# relays0.net
KiCad netlist of a schematic drawn in Altium Designer
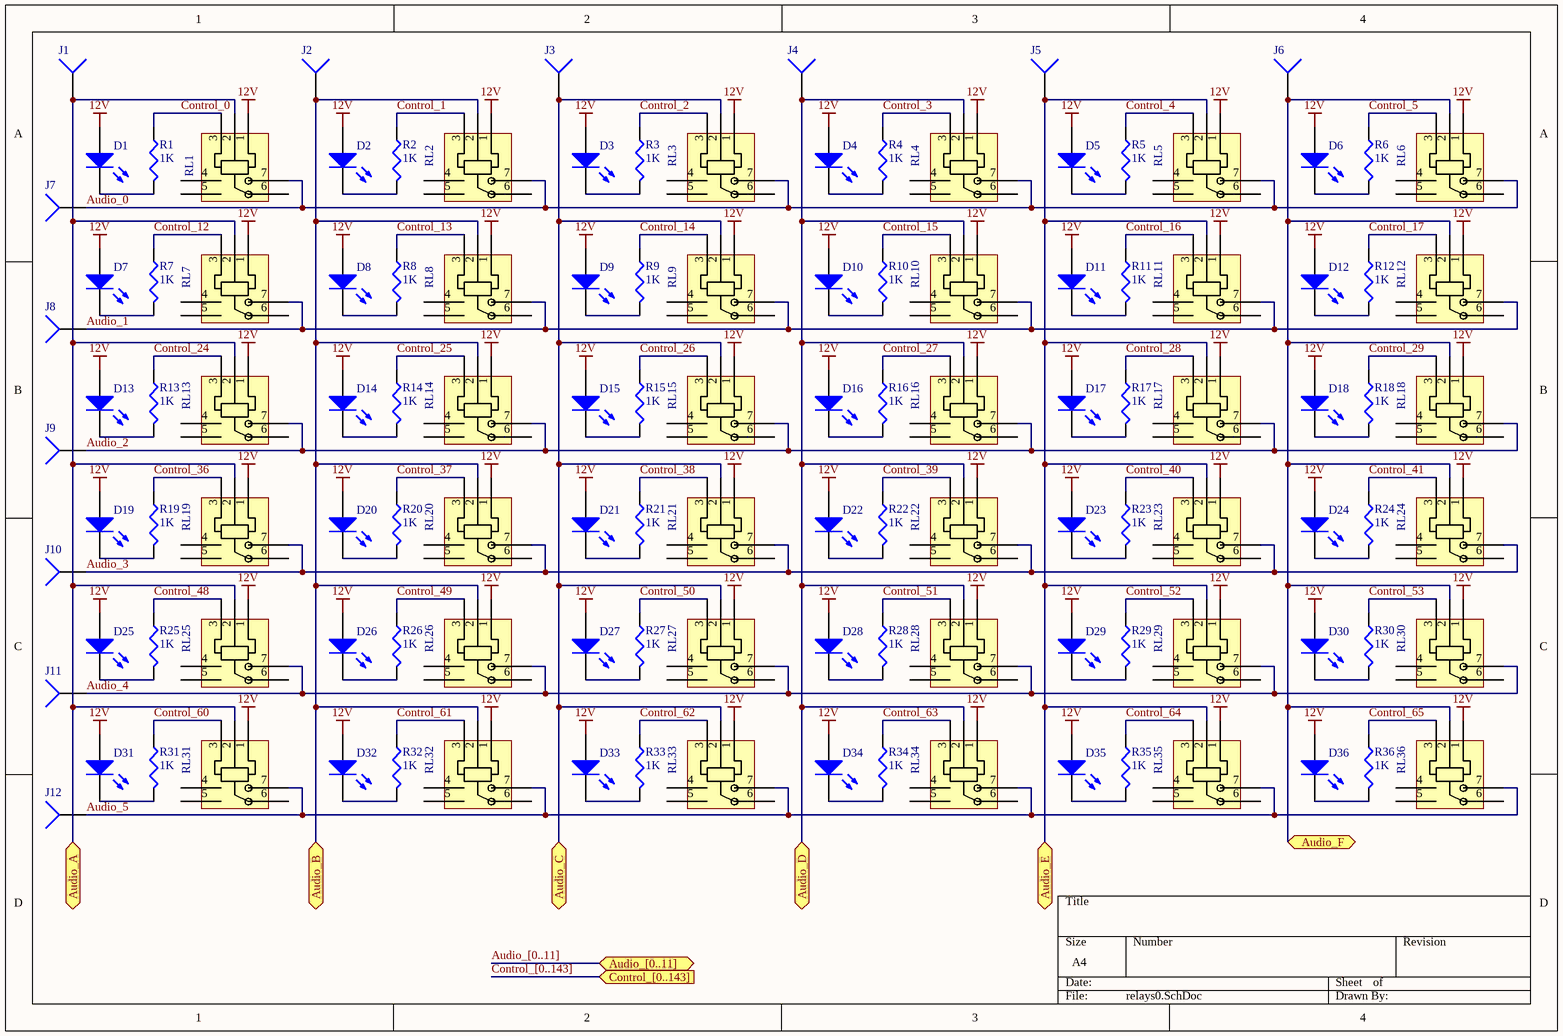
[diagram p0: relays0.SchDoc]

(export (version "E")
  (design (tool "Eeschema 10.0.6"))
  (components
    (comp (ref "D1")
      (value "LED0")
      (footprint "LED_round_5mm")
      (description "Typical INFRARED GaAs LED")
      (fields (field (name "PUBLISHER") "Altium Limited"))
      (libsource (lib "Miscellaneous Devices") (part "LED0"))
    )
    (comp (ref "D2")
      (value "LED0")
      (footprint "LED_round_5mm")
      (description "Typical INFRARED GaAs LED")
      (fields (field (name "PUBLISHER") "Altium Limited"))
      (libsource (lib "Miscellaneous Devices") (part "LED0"))
    )
    (comp (ref "D3")
      (value "LED0")
      (footprint "LED_round_5mm")
      (description "Typical INFRARED GaAs LED")
      (fields (field (name "PUBLISHER") "Altium Limited"))
      (libsource (lib "Miscellaneous Devices") (part "LED0"))
    )
    (comp (ref "D4")
      (value "LED0")
      (footprint "LED_round_5mm")
      (description "Typical INFRARED GaAs LED")
      (fields (field (name "PUBLISHER") "Altium Limited"))
      (libsource (lib "Miscellaneous Devices") (part "LED0"))
    )
    (comp (ref "D5")
      (value "LED0")
      (footprint "LED_round_5mm")
      (description "Typical INFRARED GaAs LED")
      (fields (field (name "PUBLISHER") "Altium Limited"))
      (libsource (lib "Miscellaneous Devices") (part "LED0"))
    )
    (comp (ref "D6")
      (value "LED0")
      (footprint "LED_round_5mm")
      (description "Typical INFRARED GaAs LED")
      (fields (field (name "PUBLISHER") "Altium Limited"))
      (libsource (lib "Miscellaneous Devices") (part "LED0"))
    )
    (comp (ref "D7")
      (value "LED0")
      (footprint "LED_round_5mm")
      (description "Typical INFRARED GaAs LED")
      (fields (field (name "PUBLISHER") "Altium Limited"))
      (libsource (lib "Miscellaneous Devices") (part "LED0"))
    )
    (comp (ref "D8")
      (value "LED0")
      (footprint "LED_round_5mm")
      (description "Typical INFRARED GaAs LED")
      (fields (field (name "PUBLISHER") "Altium Limited"))
      (libsource (lib "Miscellaneous Devices") (part "LED0"))
    )
    (comp (ref "D9")
      (value "LED0")
      (footprint "LED_round_5mm")
      (description "Typical INFRARED GaAs LED")
      (fields (field (name "PUBLISHER") "Altium Limited"))
      (libsource (lib "Miscellaneous Devices") (part "LED0"))
    )
    (comp (ref "D10")
      (value "LED0")
      (footprint "LED_round_5mm")
      (description "Typical INFRARED GaAs LED")
      (fields (field (name "PUBLISHER") "Altium Limited"))
      (libsource (lib "Miscellaneous Devices") (part "LED0"))
    )
    (comp (ref "D11")
      (value "LED0")
      (footprint "LED_round_5mm")
      (description "Typical INFRARED GaAs LED")
      (fields (field (name "PUBLISHER") "Altium Limited"))
      (libsource (lib "Miscellaneous Devices") (part "LED0"))
    )
    (comp (ref "D12")
      (value "LED0")
      (footprint "LED_round_5mm")
      (description "Typical INFRARED GaAs LED")
      (fields (field (name "PUBLISHER") "Altium Limited"))
      (libsource (lib "Miscellaneous Devices") (part "LED0"))
    )
    (comp (ref "D13")
      (value "LED0")
      (footprint "LED_round_5mm")
      (description "Typical INFRARED GaAs LED")
      (fields (field (name "PUBLISHER") "Altium Limited"))
      (libsource (lib "Miscellaneous Devices") (part "LED0"))
    )
    (comp (ref "D14")
      (value "LED0")
      (footprint "LED_round_5mm")
      (description "Typical INFRARED GaAs LED")
      (fields (field (name "PUBLISHER") "Altium Limited"))
      (libsource (lib "Miscellaneous Devices") (part "LED0"))
    )
    (comp (ref "D15")
      (value "LED0")
      (footprint "LED_round_5mm")
      (description "Typical INFRARED GaAs LED")
      (fields (field (name "PUBLISHER") "Altium Limited"))
      (libsource (lib "Miscellaneous Devices") (part "LED0"))
    )
    (comp (ref "D16")
      (value "LED0")
      (footprint "LED_round_5mm")
      (description "Typical INFRARED GaAs LED")
      (fields (field (name "PUBLISHER") "Altium Limited"))
      (libsource (lib "Miscellaneous Devices") (part "LED0"))
    )
    (comp (ref "D17")
      (value "LED0")
      (footprint "LED_round_5mm")
      (description "Typical INFRARED GaAs LED")
      (fields (field (name "PUBLISHER") "Altium Limited"))
      (libsource (lib "Miscellaneous Devices") (part "LED0"))
    )
    (comp (ref "D18")
      (value "LED0")
      (footprint "LED_round_5mm")
      (description "Typical INFRARED GaAs LED")
      (fields (field (name "PUBLISHER") "Altium Limited"))
      (libsource (lib "Miscellaneous Devices") (part "LED0"))
    )
    (comp (ref "D19")
      (value "LED0")
      (footprint "LED_round_5mm")
      (description "Typical INFRARED GaAs LED")
      (fields (field (name "PUBLISHER") "Altium Limited"))
      (libsource (lib "Miscellaneous Devices") (part "LED0"))
    )
    (comp (ref "D20")
      (value "LED0")
      (footprint "LED_round_5mm")
      (description "Typical INFRARED GaAs LED")
      (fields (field (name "PUBLISHER") "Altium Limited"))
      (libsource (lib "Miscellaneous Devices") (part "LED0"))
    )
    (comp (ref "D21")
      (value "LED0")
      (footprint "LED_round_5mm")
      (description "Typical INFRARED GaAs LED")
      (fields (field (name "PUBLISHER") "Altium Limited"))
      (libsource (lib "Miscellaneous Devices") (part "LED0"))
    )
    (comp (ref "D22")
      (value "LED0")
      (footprint "LED_round_5mm")
      (description "Typical INFRARED GaAs LED")
      (fields (field (name "PUBLISHER") "Altium Limited"))
      (libsource (lib "Miscellaneous Devices") (part "LED0"))
    )
    (comp (ref "D23")
      (value "LED0")
      (footprint "LED_round_5mm")
      (description "Typical INFRARED GaAs LED")
      (fields (field (name "PUBLISHER") "Altium Limited"))
      (libsource (lib "Miscellaneous Devices") (part "LED0"))
    )
    (comp (ref "D24")
      (value "LED0")
      (footprint "LED_round_5mm")
      (description "Typical INFRARED GaAs LED")
      (fields (field (name "PUBLISHER") "Altium Limited"))
      (libsource (lib "Miscellaneous Devices") (part "LED0"))
    )
    (comp (ref "D25")
      (value "LED0")
      (footprint "LED_round_5mm")
      (description "Typical INFRARED GaAs LED")
      (fields (field (name "PUBLISHER") "Altium Limited"))
      (libsource (lib "Miscellaneous Devices") (part "LED0"))
    )
    (comp (ref "D26")
      (value "LED0")
      (footprint "LED_round_5mm")
      (description "Typical INFRARED GaAs LED")
      (fields (field (name "PUBLISHER") "Altium Limited"))
      (libsource (lib "Miscellaneous Devices") (part "LED0"))
    )
    (comp (ref "D27")
      (value "LED0")
      (footprint "LED_round_5mm")
      (description "Typical INFRARED GaAs LED")
      (fields (field (name "PUBLISHER") "Altium Limited"))
      (libsource (lib "Miscellaneous Devices") (part "LED0"))
    )
    (comp (ref "D28")
      (value "LED0")
      (footprint "LED_round_5mm")
      (description "Typical INFRARED GaAs LED")
      (fields (field (name "PUBLISHER") "Altium Limited"))
      (libsource (lib "Miscellaneous Devices") (part "LED0"))
    )
    (comp (ref "D29")
      (value "LED0")
      (footprint "LED_round_5mm")
      (description "Typical INFRARED GaAs LED")
      (fields (field (name "PUBLISHER") "Altium Limited"))
      (libsource (lib "Miscellaneous Devices") (part "LED0"))
    )
    (comp (ref "D30")
      (value "LED0")
      (footprint "LED_round_5mm")
      (description "Typical INFRARED GaAs LED")
      (fields (field (name "PUBLISHER") "Altium Limited"))
      (libsource (lib "Miscellaneous Devices") (part "LED0"))
    )
    (comp (ref "D31")
      (value "LED0")
      (footprint "LED_round_5mm")
      (description "Typical INFRARED GaAs LED")
      (fields (field (name "PUBLISHER") "Altium Limited"))
      (libsource (lib "Miscellaneous Devices") (part "LED0"))
    )
    (comp (ref "D32")
      (value "LED0")
      (footprint "LED_round_5mm")
      (description "Typical INFRARED GaAs LED")
      (fields (field (name "PUBLISHER") "Altium Limited"))
      (libsource (lib "Miscellaneous Devices") (part "LED0"))
    )
    (comp (ref "D33")
      (value "LED0")
      (footprint "LED_round_5mm")
      (description "Typical INFRARED GaAs LED")
      (fields (field (name "PUBLISHER") "Altium Limited"))
      (libsource (lib "Miscellaneous Devices") (part "LED0"))
    )
    (comp (ref "D34")
      (value "LED0")
      (footprint "LED_round_5mm")
      (description "Typical INFRARED GaAs LED")
      (fields (field (name "PUBLISHER") "Altium Limited"))
      (libsource (lib "Miscellaneous Devices") (part "LED0"))
    )
    (comp (ref "D35")
      (value "LED0")
      (footprint "LED_round_5mm")
      (description "Typical INFRARED GaAs LED")
      (fields (field (name "PUBLISHER") "Altium Limited"))
      (libsource (lib "Miscellaneous Devices") (part "LED0"))
    )
    (comp (ref "D36")
      (value "LED0")
      (footprint "LED_round_5mm")
      (description "Typical INFRARED GaAs LED")
      (fields (field (name "PUBLISHER") "Altium Limited"))
      (libsource (lib "Miscellaneous Devices") (part "LED0"))
    )
    (comp (ref "J1")
      (value "Audio")
      (footprint "Conn_1_2x4")
      (description "Socket")
      (fields (field (name "PUBLISHER") "Altium Limited"))
      (libsource (lib "Miscellaneous Connectors") (part "Socket"))
    )
    (comp (ref "J2")
      (value "Audio")
      (footprint "Conn_1_2x4")
      (description "Socket")
      (fields (field (name "PUBLISHER") "Altium Limited"))
      (libsource (lib "Miscellaneous Connectors") (part "Socket"))
    )
    (comp (ref "J3")
      (value "Audio")
      (footprint "Conn_1_2x4")
      (description "Socket")
      (fields (field (name "PUBLISHER") "Altium Limited"))
      (libsource (lib "Miscellaneous Connectors") (part "Socket"))
    )
    (comp (ref "J4")
      (value "Audio")
      (footprint "Conn_1_2x4")
      (description "Socket")
      (fields (field (name "PUBLISHER") "Altium Limited"))
      (libsource (lib "Miscellaneous Connectors") (part "Socket"))
    )
    (comp (ref "J5")
      (value "Audio")
      (footprint "Conn_1_2x4")
      (description "Socket")
      (fields (field (name "PUBLISHER") "Altium Limited"))
      (libsource (lib "Miscellaneous Connectors") (part "Socket"))
    )
    (comp (ref "J6")
      (value "Audio")
      (footprint "Conn_1_2x4")
      (description "Socket")
      (fields (field (name "PUBLISHER") "Altium Limited"))
      (libsource (lib "Miscellaneous Connectors") (part "Socket"))
    )
    (comp (ref "J7")
      (value "Audio")
      (footprint "Conn_1_2x4")
      (description "Socket")
      (fields (field (name "PUBLISHER") "Altium Limited"))
      (libsource (lib "Miscellaneous Connectors") (part "Socket"))
    )
    (comp (ref "J8")
      (value "Audio")
      (footprint "Conn_1_2x4")
      (description "Socket")
      (fields (field (name "PUBLISHER") "Altium Limited"))
      (libsource (lib "Miscellaneous Connectors") (part "Socket"))
    )
    (comp (ref "J9")
      (value "Audio")
      (footprint "Conn_1_2x4")
      (description "Socket")
      (fields (field (name "PUBLISHER") "Altium Limited"))
      (libsource (lib "Miscellaneous Connectors") (part "Socket"))
    )
    (comp (ref "J10")
      (value "Audio")
      (footprint "Conn_1_2x4")
      (description "Socket")
      (fields (field (name "PUBLISHER") "Altium Limited"))
      (libsource (lib "Miscellaneous Connectors") (part "Socket"))
    )
    (comp (ref "J11")
      (value "Audio")
      (footprint "Conn_1_2x4")
      (description "Socket")
      (fields (field (name "PUBLISHER") "Altium Limited"))
      (libsource (lib "Miscellaneous Connectors") (part "Socket"))
    )
    (comp (ref "J12")
      (value "Audio")
      (footprint "Conn_1_2x4")
      (description "Socket")
      (fields (field (name "PUBLISHER") "Altium Limited"))
      (libsource (lib "Miscellaneous Connectors") (part "Socket"))
    )
    (comp (ref "R1")
      (value "1K")
      (footprint "J1-0603")
      (description "Resistor")
      (fields (field (name "Comment") "Res3") (field (name "PUBLISHER") "Altium Limited"))
      (libsource (lib "Miscellaneous Devices") (part "Res3"))
    )
    (comp (ref "R2")
      (value "1K")
      (footprint "J1-0603")
      (description "Resistor")
      (fields (field (name "Comment") "Res3") (field (name "PUBLISHER") "Altium Limited"))
      (libsource (lib "Miscellaneous Devices") (part "Res3"))
    )
    (comp (ref "R3")
      (value "1K")
      (footprint "J1-0603")
      (description "Resistor")
      (fields (field (name "Comment") "Res3") (field (name "PUBLISHER") "Altium Limited"))
      (libsource (lib "Miscellaneous Devices") (part "Res3"))
    )
    (comp (ref "R4")
      (value "1K")
      (footprint "J1-0603")
      (description "Resistor")
      (fields (field (name "Comment") "Res3") (field (name "PUBLISHER") "Altium Limited"))
      (libsource (lib "Miscellaneous Devices") (part "Res3"))
    )
    (comp (ref "R5")
      (value "1K")
      (footprint "J1-0603")
      (description "Resistor")
      (fields (field (name "Comment") "Res3") (field (name "PUBLISHER") "Altium Limited"))
      (libsource (lib "Miscellaneous Devices") (part "Res3"))
    )
    (comp (ref "R6")
      (value "1K")
      (footprint "J1-0603")
      (description "Resistor")
      (fields (field (name "Comment") "Res3") (field (name "PUBLISHER") "Altium Limited"))
      (libsource (lib "Miscellaneous Devices") (part "Res3"))
    )
    (comp (ref "R7")
      (value "1K")
      (footprint "J1-0603")
      (description "Resistor")
      (fields (field (name "Comment") "Res3") (field (name "PUBLISHER") "Altium Limited"))
      (libsource (lib "Miscellaneous Devices") (part "Res3"))
    )
    (comp (ref "R8")
      (value "1K")
      (footprint "J1-0603")
      (description "Resistor")
      (fields (field (name "Comment") "Res3") (field (name "PUBLISHER") "Altium Limited"))
      (libsource (lib "Miscellaneous Devices") (part "Res3"))
    )
    (comp (ref "R9")
      (value "1K")
      (footprint "J1-0603")
      (description "Resistor")
      (fields (field (name "Comment") "Res3") (field (name "PUBLISHER") "Altium Limited"))
      (libsource (lib "Miscellaneous Devices") (part "Res3"))
    )
    (comp (ref "R10")
      (value "1K")
      (footprint "J1-0603")
      (description "Resistor")
      (fields (field (name "Comment") "Res3") (field (name "PUBLISHER") "Altium Limited"))
      (libsource (lib "Miscellaneous Devices") (part "Res3"))
    )
    (comp (ref "R11")
      (value "1K")
      (footprint "J1-0603")
      (description "Resistor")
      (fields (field (name "Comment") "Res3") (field (name "PUBLISHER") "Altium Limited"))
      (libsource (lib "Miscellaneous Devices") (part "Res3"))
    )
    (comp (ref "R12")
      (value "1K")
      (footprint "J1-0603")
      (description "Resistor")
      (fields (field (name "Comment") "Res3") (field (name "PUBLISHER") "Altium Limited"))
      (libsource (lib "Miscellaneous Devices") (part "Res3"))
    )
    (comp (ref "R13")
      (value "1K")
      (footprint "J1-0603")
      (description "Resistor")
      (fields (field (name "Comment") "Res3") (field (name "PUBLISHER") "Altium Limited"))
      (libsource (lib "Miscellaneous Devices") (part "Res3"))
    )
    (comp (ref "R14")
      (value "1K")
      (footprint "J1-0603")
      (description "Resistor")
      (fields (field (name "Comment") "Res3") (field (name "PUBLISHER") "Altium Limited"))
      (libsource (lib "Miscellaneous Devices") (part "Res3"))
    )
    (comp (ref "R15")
      (value "1K")
      (footprint "J1-0603")
      (description "Resistor")
      (fields (field (name "Comment") "Res3") (field (name "PUBLISHER") "Altium Limited"))
      (libsource (lib "Miscellaneous Devices") (part "Res3"))
    )
    (comp (ref "R16")
      (value "1K")
      (footprint "J1-0603")
      (description "Resistor")
      (fields (field (name "Comment") "Res3") (field (name "PUBLISHER") "Altium Limited"))
      (libsource (lib "Miscellaneous Devices") (part "Res3"))
    )
    (comp (ref "R17")
      (value "1K")
      (footprint "J1-0603")
      (description "Resistor")
      (fields (field (name "Comment") "Res3") (field (name "PUBLISHER") "Altium Limited"))
      (libsource (lib "Miscellaneous Devices") (part "Res3"))
    )
    (comp (ref "R18")
      (value "1K")
      (footprint "J1-0603")
      (description "Resistor")
      (fields (field (name "Comment") "Res3") (field (name "PUBLISHER") "Altium Limited"))
      (libsource (lib "Miscellaneous Devices") (part "Res3"))
    )
    (comp (ref "R19")
      (value "1K")
      (footprint "J1-0603")
      (description "Resistor")
      (fields (field (name "Comment") "Res3") (field (name "PUBLISHER") "Altium Limited"))
      (libsource (lib "Miscellaneous Devices") (part "Res3"))
    )
    (comp (ref "R20")
      (value "1K")
      (footprint "J1-0603")
      (description "Resistor")
      (fields (field (name "Comment") "Res3") (field (name "PUBLISHER") "Altium Limited"))
      (libsource (lib "Miscellaneous Devices") (part "Res3"))
    )
    (comp (ref "R21")
      (value "1K")
      (footprint "J1-0603")
      (description "Resistor")
      (fields (field (name "Comment") "Res3") (field (name "PUBLISHER") "Altium Limited"))
      (libsource (lib "Miscellaneous Devices") (part "Res3"))
    )
    (comp (ref "R22")
      (value "1K")
      (footprint "J1-0603")
      (description "Resistor")
      (fields (field (name "Comment") "Res3") (field (name "PUBLISHER") "Altium Limited"))
      (libsource (lib "Miscellaneous Devices") (part "Res3"))
    )
    (comp (ref "R23")
      (value "1K")
      (footprint "J1-0603")
      (description "Resistor")
      (fields (field (name "Comment") "Res3") (field (name "PUBLISHER") "Altium Limited"))
      (libsource (lib "Miscellaneous Devices") (part "Res3"))
    )
    (comp (ref "R24")
      (value "1K")
      (footprint "J1-0603")
      (description "Resistor")
      (fields (field (name "Comment") "Res3") (field (name "PUBLISHER") "Altium Limited"))
      (libsource (lib "Miscellaneous Devices") (part "Res3"))
    )
    (comp (ref "R25")
      (value "1K")
      (footprint "J1-0603")
      (description "Resistor")
      (fields (field (name "Comment") "Res3") (field (name "PUBLISHER") "Altium Limited"))
      (libsource (lib "Miscellaneous Devices") (part "Res3"))
    )
    (comp (ref "R26")
      (value "1K")
      (footprint "J1-0603")
      (description "Resistor")
      (fields (field (name "Comment") "Res3") (field (name "PUBLISHER") "Altium Limited"))
      (libsource (lib "Miscellaneous Devices") (part "Res3"))
    )
    (comp (ref "R27")
      (value "1K")
      (footprint "J1-0603")
      (description "Resistor")
      (fields (field (name "Comment") "Res3") (field (name "PUBLISHER") "Altium Limited"))
      (libsource (lib "Miscellaneous Devices") (part "Res3"))
    )
    (comp (ref "R28")
      (value "1K")
      (footprint "J1-0603")
      (description "Resistor")
      (fields (field (name "Comment") "Res3") (field (name "PUBLISHER") "Altium Limited"))
      (libsource (lib "Miscellaneous Devices") (part "Res3"))
    )
    (comp (ref "R29")
      (value "1K")
      (footprint "J1-0603")
      (description "Resistor")
      (fields (field (name "Comment") "Res3") (field (name "PUBLISHER") "Altium Limited"))
      (libsource (lib "Miscellaneous Devices") (part "Res3"))
    )
    (comp (ref "R30")
      (value "1K")
      (footprint "J1-0603")
      (description "Resistor")
      (fields (field (name "Comment") "Res3") (field (name "PUBLISHER") "Altium Limited"))
      (libsource (lib "Miscellaneous Devices") (part "Res3"))
    )
    (comp (ref "R31")
      (value "1K")
      (footprint "J1-0603")
      (description "Resistor")
      (fields (field (name "Comment") "Res3") (field (name "PUBLISHER") "Altium Limited"))
      (libsource (lib "Miscellaneous Devices") (part "Res3"))
    )
    (comp (ref "R32")
      (value "1K")
      (footprint "J1-0603")
      (description "Resistor")
      (fields (field (name "Comment") "Res3") (field (name "PUBLISHER") "Altium Limited"))
      (libsource (lib "Miscellaneous Devices") (part "Res3"))
    )
    (comp (ref "R33")
      (value "1K")
      (footprint "J1-0603")
      (description "Resistor")
      (fields (field (name "Comment") "Res3") (field (name "PUBLISHER") "Altium Limited"))
      (libsource (lib "Miscellaneous Devices") (part "Res3"))
    )
    (comp (ref "R34")
      (value "1K")
      (footprint "J1-0603")
      (description "Resistor")
      (fields (field (name "Comment") "Res3") (field (name "PUBLISHER") "Altium Limited"))
      (libsource (lib "Miscellaneous Devices") (part "Res3"))
    )
    (comp (ref "R35")
      (value "1K")
      (footprint "J1-0603")
      (description "Resistor")
      (fields (field (name "Comment") "Res3") (field (name "PUBLISHER") "Altium Limited"))
      (libsource (lib "Miscellaneous Devices") (part "Res3"))
    )
    (comp (ref "R36")
      (value "1K")
      (footprint "J1-0603")
      (description "Resistor")
      (fields (field (name "Comment") "Res3") (field (name "PUBLISHER") "Altium Limited"))
      (libsource (lib "Miscellaneous Devices") (part "Res3"))
    )
    (comp (ref "RL1")
      (value "Relay")
      (footprint "Relay_FRA3")
      (description "Miniature power relay")
      (fields (field (name "PART NUMBER") "FRA3C-DC12"))
      (libsource (lib "tech-thing") (part "Relay_FRA3"))
    )
    (comp (ref "RL2")
      (value "Relay")
      (footprint "Relay_FRA3")
      (description "Miniature power relay")
      (fields (field (name "PART NUMBER") "FRA3C-DC12"))
      (libsource (lib "tech-thing") (part "Relay_FRA3"))
    )
    (comp (ref "RL3")
      (value "Relay")
      (footprint "Relay_FRA3")
      (description "Miniature power relay")
      (fields (field (name "PART NUMBER") "FRA3C-DC12"))
      (libsource (lib "tech-thing") (part "Relay_FRA3"))
    )
    (comp (ref "RL4")
      (value "Relay")
      (footprint "Relay_FRA3")
      (description "Miniature power relay")
      (fields (field (name "PART NUMBER") "FRA3C-DC12"))
      (libsource (lib "tech-thing") (part "Relay_FRA3"))
    )
    (comp (ref "RL5")
      (value "Relay")
      (footprint "Relay_FRA3")
      (description "Miniature power relay")
      (fields (field (name "PART NUMBER") "FRA3C-DC12"))
      (libsource (lib "tech-thing") (part "Relay_FRA3"))
    )
    (comp (ref "RL6")
      (value "Relay")
      (footprint "Relay_FRA3")
      (description "Miniature power relay")
      (fields (field (name "PART NUMBER") "FRA3C-DC12"))
      (libsource (lib "tech-thing") (part "Relay_FRA3"))
    )
    (comp (ref "RL7")
      (value "Relay")
      (footprint "Relay_FRA3")
      (description "Miniature power relay")
      (fields (field (name "PART NUMBER") "FRA3C-DC12"))
      (libsource (lib "tech-thing") (part "Relay_FRA3"))
    )
    (comp (ref "RL8")
      (value "Relay")
      (footprint "Relay_FRA3")
      (description "Miniature power relay")
      (fields (field (name "PART NUMBER") "FRA3C-DC12"))
      (libsource (lib "tech-thing") (part "Relay_FRA3"))
    )
    (comp (ref "RL9")
      (value "Relay")
      (footprint "Relay_FRA3")
      (description "Miniature power relay")
      (fields (field (name "PART NUMBER") "FRA3C-DC12"))
      (libsource (lib "tech-thing") (part "Relay_FRA3"))
    )
    (comp (ref "RL10")
      (value "Relay")
      (footprint "Relay_FRA3")
      (description "Miniature power relay")
      (fields (field (name "PART NUMBER") "FRA3C-DC12"))
      (libsource (lib "tech-thing") (part "Relay_FRA3"))
    )
    (comp (ref "RL11")
      (value "Relay")
      (footprint "Relay_FRA3")
      (description "Miniature power relay")
      (fields (field (name "PART NUMBER") "FRA3C-DC12"))
      (libsource (lib "tech-thing") (part "Relay_FRA3"))
    )
    (comp (ref "RL12")
      (value "Relay")
      (footprint "Relay_FRA3")
      (description "Miniature power relay")
      (fields (field (name "PART NUMBER") "FRA3C-DC12"))
      (libsource (lib "tech-thing") (part "Relay_FRA3"))
    )
    (comp (ref "RL13")
      (value "Relay")
      (footprint "Relay_FRA3")
      (description "Miniature power relay")
      (fields (field (name "PART NUMBER") "FRA3C-DC12"))
      (libsource (lib "tech-thing") (part "Relay_FRA3"))
    )
    (comp (ref "RL14")
      (value "Relay")
      (footprint "Relay_FRA3")
      (description "Miniature power relay")
      (fields (field (name "PART NUMBER") "FRA3C-DC12"))
      (libsource (lib "tech-thing") (part "Relay_FRA3"))
    )
    (comp (ref "RL15")
      (value "Relay")
      (footprint "Relay_FRA3")
      (description "Miniature power relay")
      (fields (field (name "PART NUMBER") "FRA3C-DC12"))
      (libsource (lib "tech-thing") (part "Relay_FRA3"))
    )
    (comp (ref "RL16")
      (value "Relay")
      (footprint "Relay_FRA3")
      (description "Miniature power relay")
      (fields (field (name "PART NUMBER") "FRA3C-DC12"))
      (libsource (lib "tech-thing") (part "Relay_FRA3"))
    )
    (comp (ref "RL17")
      (value "Relay")
      (footprint "Relay_FRA3")
      (description "Miniature power relay")
      (fields (field (name "PART NUMBER") "FRA3C-DC12"))
      (libsource (lib "tech-thing") (part "Relay_FRA3"))
    )
    (comp (ref "RL18")
      (value "Relay")
      (footprint "Relay_FRA3")
      (description "Miniature power relay")
      (fields (field (name "PART NUMBER") "FRA3C-DC12"))
      (libsource (lib "tech-thing") (part "Relay_FRA3"))
    )
    (comp (ref "RL19")
      (value "Relay")
      (footprint "Relay_FRA3")
      (description "Miniature power relay")
      (fields (field (name "PART NUMBER") "FRA3C-DC12"))
      (libsource (lib "tech-thing") (part "Relay_FRA3"))
    )
    (comp (ref "RL20")
      (value "Relay")
      (footprint "Relay_FRA3")
      (description "Miniature power relay")
      (fields (field (name "PART NUMBER") "FRA3C-DC12"))
      (libsource (lib "tech-thing") (part "Relay_FRA3"))
    )
    (comp (ref "RL21")
      (value "Relay")
      (footprint "Relay_FRA3")
      (description "Miniature power relay")
      (fields (field (name "PART NUMBER") "FRA3C-DC12"))
      (libsource (lib "tech-thing") (part "Relay_FRA3"))
    )
    (comp (ref "RL22")
      (value "Relay")
      (footprint "Relay_FRA3")
      (description "Miniature power relay")
      (fields (field (name "PART NUMBER") "FRA3C-DC12"))
      (libsource (lib "tech-thing") (part "Relay_FRA3"))
    )
    (comp (ref "RL23")
      (value "Relay")
      (footprint "Relay_FRA3")
      (description "Miniature power relay")
      (fields (field (name "PART NUMBER") "FRA3C-DC12"))
      (libsource (lib "tech-thing") (part "Relay_FRA3"))
    )
    (comp (ref "RL24")
      (value "Relay")
      (footprint "Relay_FRA3")
      (description "Miniature power relay")
      (fields (field (name "PART NUMBER") "FRA3C-DC12"))
      (libsource (lib "tech-thing") (part "Relay_FRA3"))
    )
    (comp (ref "RL25")
      (value "Relay")
      (footprint "Relay_FRA3")
      (description "Miniature power relay")
      (fields (field (name "PART NUMBER") "FRA3C-DC12"))
      (libsource (lib "tech-thing") (part "Relay_FRA3"))
    )
    (comp (ref "RL26")
      (value "Relay")
      (footprint "Relay_FRA3")
      (description "Miniature power relay")
      (fields (field (name "PART NUMBER") "FRA3C-DC12"))
      (libsource (lib "tech-thing") (part "Relay_FRA3"))
    )
    (comp (ref "RL27")
      (value "Relay")
      (footprint "Relay_FRA3")
      (description "Miniature power relay")
      (fields (field (name "PART NUMBER") "FRA3C-DC12"))
      (libsource (lib "tech-thing") (part "Relay_FRA3"))
    )
    (comp (ref "RL28")
      (value "Relay")
      (footprint "Relay_FRA3")
      (description "Miniature power relay")
      (fields (field (name "PART NUMBER") "FRA3C-DC12"))
      (libsource (lib "tech-thing") (part "Relay_FRA3"))
    )
    (comp (ref "RL29")
      (value "Relay")
      (footprint "Relay_FRA3")
      (description "Miniature power relay")
      (fields (field (name "PART NUMBER") "FRA3C-DC12"))
      (libsource (lib "tech-thing") (part "Relay_FRA3"))
    )
    (comp (ref "RL30")
      (value "Relay")
      (footprint "Relay_FRA3")
      (description "Miniature power relay")
      (fields (field (name "PART NUMBER") "FRA3C-DC12"))
      (libsource (lib "tech-thing") (part "Relay_FRA3"))
    )
    (comp (ref "RL31")
      (value "Relay")
      (footprint "Relay_FRA3")
      (description "Miniature power relay")
      (fields (field (name "PART NUMBER") "FRA3C-DC12"))
      (libsource (lib "tech-thing") (part "Relay_FRA3"))
    )
    (comp (ref "RL32")
      (value "Relay")
      (footprint "Relay_FRA3")
      (description "Miniature power relay")
      (fields (field (name "PART NUMBER") "FRA3C-DC12"))
      (libsource (lib "tech-thing") (part "Relay_FRA3"))
    )
    (comp (ref "RL33")
      (value "Relay")
      (footprint "Relay_FRA3")
      (description "Miniature power relay")
      (fields (field (name "PART NUMBER") "FRA3C-DC12"))
      (libsource (lib "tech-thing") (part "Relay_FRA3"))
    )
    (comp (ref "RL34")
      (value "Relay")
      (footprint "Relay_FRA3")
      (description "Miniature power relay")
      (fields (field (name "PART NUMBER") "FRA3C-DC12"))
      (libsource (lib "tech-thing") (part "Relay_FRA3"))
    )
    (comp (ref "RL35")
      (value "Relay")
      (footprint "Relay_FRA3")
      (description "Miniature power relay")
      (fields (field (name "PART NUMBER") "FRA3C-DC12"))
      (libsource (lib "tech-thing") (part "Relay_FRA3"))
    )
    (comp (ref "RL36")
      (value "Relay")
      (footprint "Relay_FRA3")
      (description "Miniature power relay")
      (fields (field (name "PART NUMBER") "FRA3C-DC12"))
      (libsource (lib "tech-thing") (part "Relay_FRA3"))
    )
  )
  (nets
    (net (code "115") (name "/Audio_0") (class "Default")
      (node (ref "J7") (pin "1") (pinfunction "1_1") (pintype "passive"))
      (node (ref "RL1") (pin "7") (pintype "passive"))
      (node (ref "RL2") (pin "7") (pintype "passive"))
      (node (ref "RL3") (pin "7") (pintype "passive"))
      (node (ref "RL4") (pin "7") (pintype "passive"))
      (node (ref "RL5") (pin "7") (pintype "passive"))
      (node (ref "RL6") (pin "7") (pintype "passive"))
    )
    (net (code "116") (name "/Audio_1") (class "Default")
      (node (ref "J8") (pin "1") (pinfunction "1_1") (pintype "passive"))
      (node (ref "RL10") (pin "7") (pintype "passive"))
      (node (ref "RL11") (pin "7") (pintype "passive"))
      (node (ref "RL12") (pin "7") (pintype "passive"))
      (node (ref "RL7") (pin "7") (pintype "passive"))
      (node (ref "RL8") (pin "7") (pintype "passive"))
      (node (ref "RL9") (pin "7") (pintype "passive"))
    )
    (net (code "117") (name "/Audio_2") (class "Default")
      (node (ref "J9") (pin "1") (pinfunction "1_1") (pintype "passive"))
      (node (ref "RL13") (pin "7") (pintype "passive"))
      (node (ref "RL14") (pin "7") (pintype "passive"))
      (node (ref "RL15") (pin "7") (pintype "passive"))
      (node (ref "RL16") (pin "7") (pintype "passive"))
      (node (ref "RL17") (pin "7") (pintype "passive"))
      (node (ref "RL18") (pin "7") (pintype "passive"))
    )
    (net (code "118") (name "/Audio_3") (class "Default")
      (node (ref "J10") (pin "1") (pinfunction "1_1") (pintype "passive"))
      (node (ref "RL19") (pin "7") (pintype "passive"))
      (node (ref "RL20") (pin "7") (pintype "passive"))
      (node (ref "RL21") (pin "7") (pintype "passive"))
      (node (ref "RL22") (pin "7") (pintype "passive"))
      (node (ref "RL23") (pin "7") (pintype "passive"))
      (node (ref "RL24") (pin "7") (pintype "passive"))
    )
    (net (code "119") (name "/Audio_4") (class "Default")
      (node (ref "J11") (pin "1") (pinfunction "1_1") (pintype "passive"))
      (node (ref "RL25") (pin "7") (pintype "passive"))
      (node (ref "RL26") (pin "7") (pintype "passive"))
      (node (ref "RL27") (pin "7") (pintype "passive"))
      (node (ref "RL28") (pin "7") (pintype "passive"))
      (node (ref "RL29") (pin "7") (pintype "passive"))
      (node (ref "RL30") (pin "7") (pintype "passive"))
    )
    (net (code "120") (name "/Audio_5") (class "Default")
      (node (ref "J12") (pin "1") (pinfunction "1_1") (pintype "passive"))
      (node (ref "RL31") (pin "7") (pintype "passive"))
      (node (ref "RL32") (pin "7") (pintype "passive"))
      (node (ref "RL33") (pin "7") (pintype "passive"))
      (node (ref "RL34") (pin "7") (pintype "passive"))
      (node (ref "RL35") (pin "7") (pintype "passive"))
      (node (ref "RL36") (pin "7") (pintype "passive"))
    )
    (net (code "121") (name "/Audio_A") (class "Default")
      (node (ref "J1") (pin "1") (pinfunction "1_1") (pintype "passive"))
      (node (ref "RL1") (pin "2") (pintype "passive"))
      (node (ref "RL13") (pin "2") (pintype "passive"))
      (node (ref "RL19") (pin "2") (pintype "passive"))
      (node (ref "RL25") (pin "2") (pintype "passive"))
      (node (ref "RL31") (pin "2") (pintype "passive"))
      (node (ref "RL7") (pin "2") (pintype "passive"))
    )
    (net (code "122") (name "/Audio_B") (class "Default")
      (node (ref "J2") (pin "1") (pinfunction "1_1") (pintype "passive"))
      (node (ref "RL14") (pin "2") (pintype "passive"))
      (node (ref "RL2") (pin "2") (pintype "passive"))
      (node (ref "RL20") (pin "2") (pintype "passive"))
      (node (ref "RL26") (pin "2") (pintype "passive"))
      (node (ref "RL32") (pin "2") (pintype "passive"))
      (node (ref "RL8") (pin "2") (pintype "passive"))
    )
    (net (code "123") (name "/Audio_C") (class "Default")
      (node (ref "J3") (pin "1") (pinfunction "1_1") (pintype "passive"))
      (node (ref "RL15") (pin "2") (pintype "passive"))
      (node (ref "RL21") (pin "2") (pintype "passive"))
      (node (ref "RL27") (pin "2") (pintype "passive"))
      (node (ref "RL3") (pin "2") (pintype "passive"))
      (node (ref "RL33") (pin "2") (pintype "passive"))
      (node (ref "RL9") (pin "2") (pintype "passive"))
    )
    (net (code "124") (name "/Audio_D") (class "Default")
      (node (ref "J4") (pin "1") (pinfunction "1_1") (pintype "passive"))
      (node (ref "RL10") (pin "2") (pintype "passive"))
      (node (ref "RL16") (pin "2") (pintype "passive"))
      (node (ref "RL22") (pin "2") (pintype "passive"))
      (node (ref "RL28") (pin "2") (pintype "passive"))
      (node (ref "RL34") (pin "2") (pintype "passive"))
      (node (ref "RL4") (pin "2") (pintype "passive"))
    )
    (net (code "125") (name "/Audio_E") (class "Default")
      (node (ref "J5") (pin "1") (pinfunction "1_1") (pintype "passive"))
      (node (ref "RL11") (pin "2") (pintype "passive"))
      (node (ref "RL17") (pin "2") (pintype "passive"))
      (node (ref "RL23") (pin "2") (pintype "passive"))
      (node (ref "RL29") (pin "2") (pintype "passive"))
      (node (ref "RL35") (pin "2") (pintype "passive"))
      (node (ref "RL5") (pin "2") (pintype "passive"))
    )
    (net (code "126") (name "/Audio_F") (class "Default")
      (node (ref "J6") (pin "1") (pinfunction "1_1") (pintype "passive"))
      (node (ref "RL12") (pin "2") (pintype "passive"))
      (node (ref "RL18") (pin "2") (pintype "passive"))
      (node (ref "RL24") (pin "2") (pintype "passive"))
      (node (ref "RL30") (pin "2") (pintype "passive"))
      (node (ref "RL36") (pin "2") (pintype "passive"))
      (node (ref "RL6") (pin "2") (pintype "passive"))
    )
    (net (code "128") (name "/Control_0") (class "Default")
      (node (ref "R1") (pin "1") (pinfunction "1_1") (pintype "passive"))
      (node (ref "RL1") (pin "3") (pintype "passive"))
    )
    (net (code "129") (name "/Control_1") (class "Default")
      (node (ref "R2") (pin "1") (pinfunction "1_1") (pintype "passive"))
      (node (ref "RL2") (pin "3") (pintype "passive"))
    )
    (net (code "130") (name "/Control_2") (class "Default")
      (node (ref "R3") (pin "1") (pinfunction "1_1") (pintype "passive"))
      (node (ref "RL3") (pin "3") (pintype "passive"))
    )
    (net (code "131") (name "/Control_3") (class "Default")
      (node (ref "R4") (pin "1") (pinfunction "1_1") (pintype "passive"))
      (node (ref "RL4") (pin "3") (pintype "passive"))
    )
    (net (code "132") (name "/Control_4") (class "Default")
      (node (ref "R5") (pin "1") (pinfunction "1_1") (pintype "passive"))
      (node (ref "RL5") (pin "3") (pintype "passive"))
    )
    (net (code "133") (name "/Control_5") (class "Default")
      (node (ref "R6") (pin "1") (pinfunction "1_1") (pintype "passive"))
      (node (ref "RL6") (pin "3") (pintype "passive"))
    )
    (net (code "134") (name "/Control_12") (class "Default")
      (node (ref "R7") (pin "1") (pinfunction "1_1") (pintype "passive"))
      (node (ref "RL7") (pin "3") (pintype "passive"))
    )
    (net (code "135") (name "/Control_13") (class "Default")
      (node (ref "R8") (pin "1") (pinfunction "1_1") (pintype "passive"))
      (node (ref "RL8") (pin "3") (pintype "passive"))
    )
    (net (code "136") (name "/Control_14") (class "Default")
      (node (ref "R9") (pin "1") (pinfunction "1_1") (pintype "passive"))
      (node (ref "RL9") (pin "3") (pintype "passive"))
    )
    (net (code "137") (name "/Control_15") (class "Default")
      (node (ref "R10") (pin "1") (pinfunction "1_1") (pintype "passive"))
      (node (ref "RL10") (pin "3") (pintype "passive"))
    )
    (net (code "138") (name "/Control_16") (class "Default")
      (node (ref "R11") (pin "1") (pinfunction "1_1") (pintype "passive"))
      (node (ref "RL11") (pin "3") (pintype "passive"))
    )
    (net (code "139") (name "/Control_17") (class "Default")
      (node (ref "R12") (pin "1") (pinfunction "1_1") (pintype "passive"))
      (node (ref "RL12") (pin "3") (pintype "passive"))
    )
    (net (code "140") (name "/Control_24") (class "Default")
      (node (ref "R13") (pin "1") (pinfunction "1_1") (pintype "passive"))
      (node (ref "RL13") (pin "3") (pintype "passive"))
    )
    (net (code "141") (name "/Control_25") (class "Default")
      (node (ref "R14") (pin "1") (pinfunction "1_1") (pintype "passive"))
      (node (ref "RL14") (pin "3") (pintype "passive"))
    )
    (net (code "142") (name "/Control_26") (class "Default")
      (node (ref "R15") (pin "1") (pinfunction "1_1") (pintype "passive"))
      (node (ref "RL15") (pin "3") (pintype "passive"))
    )
    (net (code "143") (name "/Control_27") (class "Default")
      (node (ref "R16") (pin "1") (pinfunction "1_1") (pintype "passive"))
      (node (ref "RL16") (pin "3") (pintype "passive"))
    )
    (net (code "144") (name "/Control_28") (class "Default")
      (node (ref "R17") (pin "1") (pinfunction "1_1") (pintype "passive"))
      (node (ref "RL17") (pin "3") (pintype "passive"))
    )
    (net (code "145") (name "/Control_29") (class "Default")
      (node (ref "R18") (pin "1") (pinfunction "1_1") (pintype "passive"))
      (node (ref "RL18") (pin "3") (pintype "passive"))
    )
    (net (code "146") (name "/Control_36") (class "Default")
      (node (ref "R19") (pin "1") (pinfunction "1_1") (pintype "passive"))
      (node (ref "RL19") (pin "3") (pintype "passive"))
    )
    (net (code "147") (name "/Control_37") (class "Default")
      (node (ref "R20") (pin "1") (pinfunction "1_1") (pintype "passive"))
      (node (ref "RL20") (pin "3") (pintype "passive"))
    )
    (net (code "148") (name "/Control_38") (class "Default")
      (node (ref "R21") (pin "1") (pinfunction "1_1") (pintype "passive"))
      (node (ref "RL21") (pin "3") (pintype "passive"))
    )
    (net (code "149") (name "/Control_39") (class "Default")
      (node (ref "R22") (pin "1") (pinfunction "1_1") (pintype "passive"))
      (node (ref "RL22") (pin "3") (pintype "passive"))
    )
    (net (code "150") (name "/Control_40") (class "Default")
      (node (ref "R23") (pin "1") (pinfunction "1_1") (pintype "passive"))
      (node (ref "RL23") (pin "3") (pintype "passive"))
    )
    (net (code "151") (name "/Control_41") (class "Default")
      (node (ref "R24") (pin "1") (pinfunction "1_1") (pintype "passive"))
      (node (ref "RL24") (pin "3") (pintype "passive"))
    )
    (net (code "152") (name "/Control_48") (class "Default")
      (node (ref "R25") (pin "1") (pinfunction "1_1") (pintype "passive"))
      (node (ref "RL25") (pin "3") (pintype "passive"))
    )
    (net (code "153") (name "/Control_49") (class "Default")
      (node (ref "R26") (pin "1") (pinfunction "1_1") (pintype "passive"))
      (node (ref "RL26") (pin "3") (pintype "passive"))
    )
    (net (code "154") (name "/Control_50") (class "Default")
      (node (ref "R27") (pin "1") (pinfunction "1_1") (pintype "passive"))
      (node (ref "RL27") (pin "3") (pintype "passive"))
    )
    (net (code "155") (name "/Control_51") (class "Default")
      (node (ref "R28") (pin "1") (pinfunction "1_1") (pintype "passive"))
      (node (ref "RL28") (pin "3") (pintype "passive"))
    )
    (net (code "156") (name "/Control_52") (class "Default")
      (node (ref "R29") (pin "1") (pinfunction "1_1") (pintype "passive"))
      (node (ref "RL29") (pin "3") (pintype "passive"))
    )
    (net (code "157") (name "/Control_53") (class "Default")
      (node (ref "R30") (pin "1") (pinfunction "1_1") (pintype "passive"))
      (node (ref "RL30") (pin "3") (pintype "passive"))
    )
    (net (code "158") (name "/Control_60") (class "Default")
      (node (ref "R31") (pin "1") (pinfunction "1_1") (pintype "passive"))
      (node (ref "RL31") (pin "3") (pintype "passive"))
    )
    (net (code "159") (name "/Control_61") (class "Default")
      (node (ref "R32") (pin "1") (pinfunction "1_1") (pintype "passive"))
      (node (ref "RL32") (pin "3") (pintype "passive"))
    )
    (net (code "160") (name "/Control_62") (class "Default")
      (node (ref "R33") (pin "1") (pinfunction "1_1") (pintype "passive"))
      (node (ref "RL33") (pin "3") (pintype "passive"))
    )
    (net (code "161") (name "/Control_63") (class "Default")
      (node (ref "R34") (pin "1") (pinfunction "1_1") (pintype "passive"))
      (node (ref "RL34") (pin "3") (pintype "passive"))
    )
    (net (code "162") (name "/Control_64") (class "Default")
      (node (ref "R35") (pin "1") (pinfunction "1_1") (pintype "passive"))
      (node (ref "RL35") (pin "3") (pintype "passive"))
    )
    (net (code "163") (name "/Control_65") (class "Default")
      (node (ref "R36") (pin "1") (pinfunction "1_1") (pintype "passive"))
      (node (ref "RL36") (pin "3") (pintype "passive"))
    )
    (net (code "165") (name "12V") (class "Default")
      (node (ref "D1") (pin "1") (pinfunction "A_1") (pintype "passive"))
      (node (ref "D10") (pin "1") (pinfunction "A_1") (pintype "passive"))
      (node (ref "D11") (pin "1") (pinfunction "A_1") (pintype "passive"))
      (node (ref "D12") (pin "1") (pinfunction "A_1") (pintype "passive"))
      (node (ref "D13") (pin "1") (pinfunction "A_1") (pintype "passive"))
      (node (ref "D14") (pin "1") (pinfunction "A_1") (pintype "passive"))
      (node (ref "D15") (pin "1") (pinfunction "A_1") (pintype "passive"))
      (node (ref "D16") (pin "1") (pinfunction "A_1") (pintype "passive"))
      (node (ref "D17") (pin "1") (pinfunction "A_1") (pintype "passive"))
      (node (ref "D18") (pin "1") (pinfunction "A_1") (pintype "passive"))
      (node (ref "D19") (pin "1") (pinfunction "A_1") (pintype "passive"))
      (node (ref "D2") (pin "1") (pinfunction "A_1") (pintype "passive"))
      (node (ref "D20") (pin "1") (pinfunction "A_1") (pintype "passive"))
      (node (ref "D21") (pin "1") (pinfunction "A_1") (pintype "passive"))
      (node (ref "D22") (pin "1") (pinfunction "A_1") (pintype "passive"))
      (node (ref "D23") (pin "1") (pinfunction "A_1") (pintype "passive"))
      (node (ref "D24") (pin "1") (pinfunction "A_1") (pintype "passive"))
      (node (ref "D25") (pin "1") (pinfunction "A_1") (pintype "passive"))
      (node (ref "D26") (pin "1") (pinfunction "A_1") (pintype "passive"))
      (node (ref "D27") (pin "1") (pinfunction "A_1") (pintype "passive"))
      (node (ref "D28") (pin "1") (pinfunction "A_1") (pintype "passive"))
      (node (ref "D29") (pin "1") (pinfunction "A_1") (pintype "passive"))
      (node (ref "D3") (pin "1") (pinfunction "A_1") (pintype "passive"))
      (node (ref "D30") (pin "1") (pinfunction "A_1") (pintype "passive"))
      (node (ref "D31") (pin "1") (pinfunction "A_1") (pintype "passive"))
      (node (ref "D32") (pin "1") (pinfunction "A_1") (pintype "passive"))
      (node (ref "D33") (pin "1") (pinfunction "A_1") (pintype "passive"))
      (node (ref "D34") (pin "1") (pinfunction "A_1") (pintype "passive"))
      (node (ref "D35") (pin "1") (pinfunction "A_1") (pintype "passive"))
      (node (ref "D36") (pin "1") (pinfunction "A_1") (pintype "passive"))
      (node (ref "D4") (pin "1") (pinfunction "A_1") (pintype "passive"))
      (node (ref "D5") (pin "1") (pinfunction "A_1") (pintype "passive"))
      (node (ref "D6") (pin "1") (pinfunction "A_1") (pintype "passive"))
      (node (ref "D7") (pin "1") (pinfunction "A_1") (pintype "passive"))
      (node (ref "D8") (pin "1") (pinfunction "A_1") (pintype "passive"))
      (node (ref "D9") (pin "1") (pinfunction "A_1") (pintype "passive"))
      (node (ref "RL1") (pin "1") (pintype "passive"))
      (node (ref "RL10") (pin "1") (pintype "passive"))
      (node (ref "RL11") (pin "1") (pintype "passive"))
      (node (ref "RL12") (pin "1") (pintype "passive"))
      (node (ref "RL13") (pin "1") (pintype "passive"))
      (node (ref "RL14") (pin "1") (pintype "passive"))
      (node (ref "RL15") (pin "1") (pintype "passive"))
      (node (ref "RL16") (pin "1") (pintype "passive"))
      (node (ref "RL17") (pin "1") (pintype "passive"))
      (node (ref "RL18") (pin "1") (pintype "passive"))
      (node (ref "RL19") (pin "1") (pintype "passive"))
      (node (ref "RL2") (pin "1") (pintype "passive"))
      (node (ref "RL20") (pin "1") (pintype "passive"))
      (node (ref "RL21") (pin "1") (pintype "passive"))
      (node (ref "RL22") (pin "1") (pintype "passive"))
      (node (ref "RL23") (pin "1") (pintype "passive"))
      (node (ref "RL24") (pin "1") (pintype "passive"))
      (node (ref "RL25") (pin "1") (pintype "passive"))
      (node (ref "RL26") (pin "1") (pintype "passive"))
      (node (ref "RL27") (pin "1") (pintype "passive"))
      (node (ref "RL28") (pin "1") (pintype "passive"))
      (node (ref "RL29") (pin "1") (pintype "passive"))
      (node (ref "RL3") (pin "1") (pintype "passive"))
      (node (ref "RL30") (pin "1") (pintype "passive"))
      (node (ref "RL31") (pin "1") (pintype "passive"))
      (node (ref "RL32") (pin "1") (pintype "passive"))
      (node (ref "RL33") (pin "1") (pintype "passive"))
      (node (ref "RL34") (pin "1") (pintype "passive"))
      (node (ref "RL35") (pin "1") (pintype "passive"))
      (node (ref "RL36") (pin "1") (pintype "passive"))
      (node (ref "RL4") (pin "1") (pintype "passive"))
      (node (ref "RL5") (pin "1") (pintype "passive"))
      (node (ref "RL6") (pin "1") (pintype "passive"))
      (node (ref "RL7") (pin "1") (pintype "passive"))
      (node (ref "RL8") (pin "1") (pintype "passive"))
      (node (ref "RL9") (pin "1") (pintype "passive"))
    )
    (net (code "166") (name "Net-(D1-K)") (class "Default")
      (node (ref "D1") (pin "2") (pinfunction "K_2") (pintype "passive"))
      (node (ref "R1") (pin "2") (pinfunction "2_2") (pintype "passive"))
    )
    (net (code "167") (name "Net-(D2-K)") (class "Default")
      (node (ref "D2") (pin "2") (pinfunction "K_2") (pintype "passive"))
      (node (ref "R2") (pin "2") (pinfunction "2_2") (pintype "passive"))
    )
    (net (code "168") (name "Net-(D3-K)") (class "Default")
      (node (ref "D3") (pin "2") (pinfunction "K_2") (pintype "passive"))
      (node (ref "R3") (pin "2") (pinfunction "2_2") (pintype "passive"))
    )
    (net (code "169") (name "Net-(D4-K)") (class "Default")
      (node (ref "D4") (pin "2") (pinfunction "K_2") (pintype "passive"))
      (node (ref "R4") (pin "2") (pinfunction "2_2") (pintype "passive"))
    )
    (net (code "170") (name "Net-(D5-K)") (class "Default")
      (node (ref "D5") (pin "2") (pinfunction "K_2") (pintype "passive"))
      (node (ref "R5") (pin "2") (pinfunction "2_2") (pintype "passive"))
    )
    (net (code "171") (name "Net-(D6-K)") (class "Default")
      (node (ref "D6") (pin "2") (pinfunction "K_2") (pintype "passive"))
      (node (ref "R6") (pin "2") (pinfunction "2_2") (pintype "passive"))
    )
    (net (code "172") (name "Net-(D7-K)") (class "Default")
      (node (ref "D7") (pin "2") (pinfunction "K_2") (pintype "passive"))
      (node (ref "R7") (pin "2") (pinfunction "2_2") (pintype "passive"))
    )
    (net (code "173") (name "Net-(D8-K)") (class "Default")
      (node (ref "D8") (pin "2") (pinfunction "K_2") (pintype "passive"))
      (node (ref "R8") (pin "2") (pinfunction "2_2") (pintype "passive"))
    )
    (net (code "174") (name "Net-(D9-K)") (class "Default")
      (node (ref "D9") (pin "2") (pinfunction "K_2") (pintype "passive"))
      (node (ref "R9") (pin "2") (pinfunction "2_2") (pintype "passive"))
    )
    (net (code "175") (name "Net-(D10-K)") (class "Default")
      (node (ref "D10") (pin "2") (pinfunction "K_2") (pintype "passive"))
      (node (ref "R10") (pin "2") (pinfunction "2_2") (pintype "passive"))
    )
    (net (code "176") (name "Net-(D11-K)") (class "Default")
      (node (ref "D11") (pin "2") (pinfunction "K_2") (pintype "passive"))
      (node (ref "R11") (pin "2") (pinfunction "2_2") (pintype "passive"))
    )
    (net (code "177") (name "Net-(D12-K)") (class "Default")
      (node (ref "D12") (pin "2") (pinfunction "K_2") (pintype "passive"))
      (node (ref "R12") (pin "2") (pinfunction "2_2") (pintype "passive"))
    )
    (net (code "178") (name "Net-(D13-K)") (class "Default")
      (node (ref "D13") (pin "2") (pinfunction "K_2") (pintype "passive"))
      (node (ref "R13") (pin "2") (pinfunction "2_2") (pintype "passive"))
    )
    (net (code "179") (name "Net-(D14-K)") (class "Default")
      (node (ref "D14") (pin "2") (pinfunction "K_2") (pintype "passive"))
      (node (ref "R14") (pin "2") (pinfunction "2_2") (pintype "passive"))
    )
    (net (code "180") (name "Net-(D15-K)") (class "Default")
      (node (ref "D15") (pin "2") (pinfunction "K_2") (pintype "passive"))
      (node (ref "R15") (pin "2") (pinfunction "2_2") (pintype "passive"))
    )
    (net (code "181") (name "Net-(D16-K)") (class "Default")
      (node (ref "D16") (pin "2") (pinfunction "K_2") (pintype "passive"))
      (node (ref "R16") (pin "2") (pinfunction "2_2") (pintype "passive"))
    )
    (net (code "182") (name "Net-(D17-K)") (class "Default")
      (node (ref "D17") (pin "2") (pinfunction "K_2") (pintype "passive"))
      (node (ref "R17") (pin "2") (pinfunction "2_2") (pintype "passive"))
    )
    (net (code "183") (name "Net-(D18-K)") (class "Default")
      (node (ref "D18") (pin "2") (pinfunction "K_2") (pintype "passive"))
      (node (ref "R18") (pin "2") (pinfunction "2_2") (pintype "passive"))
    )
    (net (code "184") (name "Net-(D19-K)") (class "Default")
      (node (ref "D19") (pin "2") (pinfunction "K_2") (pintype "passive"))
      (node (ref "R19") (pin "2") (pinfunction "2_2") (pintype "passive"))
    )
    (net (code "185") (name "Net-(D20-K)") (class "Default")
      (node (ref "D20") (pin "2") (pinfunction "K_2") (pintype "passive"))
      (node (ref "R20") (pin "2") (pinfunction "2_2") (pintype "passive"))
    )
    (net (code "186") (name "Net-(D21-K)") (class "Default")
      (node (ref "D21") (pin "2") (pinfunction "K_2") (pintype "passive"))
      (node (ref "R21") (pin "2") (pinfunction "2_2") (pintype "passive"))
    )
    (net (code "187") (name "Net-(D22-K)") (class "Default")
      (node (ref "D22") (pin "2") (pinfunction "K_2") (pintype "passive"))
      (node (ref "R22") (pin "2") (pinfunction "2_2") (pintype "passive"))
    )
    (net (code "188") (name "Net-(D23-K)") (class "Default")
      (node (ref "D23") (pin "2") (pinfunction "K_2") (pintype "passive"))
      (node (ref "R23") (pin "2") (pinfunction "2_2") (pintype "passive"))
    )
    (net (code "189") (name "Net-(D24-K)") (class "Default")
      (node (ref "D24") (pin "2") (pinfunction "K_2") (pintype "passive"))
      (node (ref "R24") (pin "2") (pinfunction "2_2") (pintype "passive"))
    )
    (net (code "190") (name "Net-(D25-K)") (class "Default")
      (node (ref "D25") (pin "2") (pinfunction "K_2") (pintype "passive"))
      (node (ref "R25") (pin "2") (pinfunction "2_2") (pintype "passive"))
    )
    (net (code "191") (name "Net-(D26-K)") (class "Default")
      (node (ref "D26") (pin "2") (pinfunction "K_2") (pintype "passive"))
      (node (ref "R26") (pin "2") (pinfunction "2_2") (pintype "passive"))
    )
    (net (code "192") (name "Net-(D27-K)") (class "Default")
      (node (ref "D27") (pin "2") (pinfunction "K_2") (pintype "passive"))
      (node (ref "R27") (pin "2") (pinfunction "2_2") (pintype "passive"))
    )
    (net (code "193") (name "Net-(D28-K)") (class "Default")
      (node (ref "D28") (pin "2") (pinfunction "K_2") (pintype "passive"))
      (node (ref "R28") (pin "2") (pinfunction "2_2") (pintype "passive"))
    )
    (net (code "194") (name "Net-(D29-K)") (class "Default")
      (node (ref "D29") (pin "2") (pinfunction "K_2") (pintype "passive"))
      (node (ref "R29") (pin "2") (pinfunction "2_2") (pintype "passive"))
    )
    (net (code "195") (name "Net-(D30-K)") (class "Default")
      (node (ref "D30") (pin "2") (pinfunction "K_2") (pintype "passive"))
      (node (ref "R30") (pin "2") (pinfunction "2_2") (pintype "passive"))
    )
    (net (code "196") (name "Net-(D31-K)") (class "Default")
      (node (ref "D31") (pin "2") (pinfunction "K_2") (pintype "passive"))
      (node (ref "R31") (pin "2") (pinfunction "2_2") (pintype "passive"))
    )
    (net (code "197") (name "Net-(D32-K)") (class "Default")
      (node (ref "D32") (pin "2") (pinfunction "K_2") (pintype "passive"))
      (node (ref "R32") (pin "2") (pinfunction "2_2") (pintype "passive"))
    )
    (net (code "198") (name "Net-(D33-K)") (class "Default")
      (node (ref "D33") (pin "2") (pinfunction "K_2") (pintype "passive"))
      (node (ref "R33") (pin "2") (pinfunction "2_2") (pintype "passive"))
    )
    (net (code "199") (name "Net-(D34-K)") (class "Default")
      (node (ref "D34") (pin "2") (pinfunction "K_2") (pintype "passive"))
      (node (ref "R34") (pin "2") (pinfunction "2_2") (pintype "passive"))
    )
    (net (code "200") (name "Net-(D35-K)") (class "Default")
      (node (ref "D35") (pin "2") (pinfunction "K_2") (pintype "passive"))
      (node (ref "R35") (pin "2") (pinfunction "2_2") (pintype "passive"))
    )
    (net (code "201") (name "Net-(D36-K)") (class "Default")
      (node (ref "D36") (pin "2") (pinfunction "K_2") (pintype "passive"))
      (node (ref "R36") (pin "2") (pinfunction "2_2") (pintype "passive"))
    )
    (net (code "202") (name "unconnected-(RL1-Pad4)") (class "Default")
      (node (ref "RL1") (pin "4") (pintype "passive"))
    )
    (net (code "203") (name "unconnected-(RL1-Pad5)") (class "Default")
      (node (ref "RL1") (pin "5") (pintype "passive"))
    )
    (net (code "204") (name "unconnected-(RL1-Pad6)") (class "Default")
      (node (ref "RL1") (pin "6") (pintype "passive"))
    )
    (net (code "205") (name "unconnected-(RL2-Pad4)") (class "Default")
      (node (ref "RL2") (pin "4") (pintype "passive"))
    )
    (net (code "206") (name "unconnected-(RL2-Pad5)") (class "Default")
      (node (ref "RL2") (pin "5") (pintype "passive"))
    )
    (net (code "207") (name "unconnected-(RL2-Pad6)") (class "Default")
      (node (ref "RL2") (pin "6") (pintype "passive"))
    )
    (net (code "208") (name "unconnected-(RL3-Pad4)") (class "Default")
      (node (ref "RL3") (pin "4") (pintype "passive"))
    )
    (net (code "209") (name "unconnected-(RL3-Pad5)") (class "Default")
      (node (ref "RL3") (pin "5") (pintype "passive"))
    )
    (net (code "210") (name "unconnected-(RL3-Pad6)") (class "Default")
      (node (ref "RL3") (pin "6") (pintype "passive"))
    )
    (net (code "211") (name "unconnected-(RL4-Pad4)") (class "Default")
      (node (ref "RL4") (pin "4") (pintype "passive"))
    )
    (net (code "212") (name "unconnected-(RL4-Pad5)") (class "Default")
      (node (ref "RL4") (pin "5") (pintype "passive"))
    )
    (net (code "213") (name "unconnected-(RL4-Pad6)") (class "Default")
      (node (ref "RL4") (pin "6") (pintype "passive"))
    )
    (net (code "214") (name "unconnected-(RL5-Pad4)") (class "Default")
      (node (ref "RL5") (pin "4") (pintype "passive"))
    )
    (net (code "215") (name "unconnected-(RL5-Pad5)") (class "Default")
      (node (ref "RL5") (pin "5") (pintype "passive"))
    )
    (net (code "216") (name "unconnected-(RL5-Pad6)") (class "Default")
      (node (ref "RL5") (pin "6") (pintype "passive"))
    )
    (net (code "217") (name "unconnected-(RL6-Pad4)") (class "Default")
      (node (ref "RL6") (pin "4") (pintype "passive"))
    )
    (net (code "218") (name "unconnected-(RL6-Pad5)") (class "Default")
      (node (ref "RL6") (pin "5") (pintype "passive"))
    )
    (net (code "219") (name "unconnected-(RL6-Pad6)") (class "Default")
      (node (ref "RL6") (pin "6") (pintype "passive"))
    )
    (net (code "220") (name "unconnected-(RL7-Pad4)") (class "Default")
      (node (ref "RL7") (pin "4") (pintype "passive"))
    )
    (net (code "221") (name "unconnected-(RL7-Pad5)") (class "Default")
      (node (ref "RL7") (pin "5") (pintype "passive"))
    )
    (net (code "222") (name "unconnected-(RL7-Pad6)") (class "Default")
      (node (ref "RL7") (pin "6") (pintype "passive"))
    )
    (net (code "223") (name "unconnected-(RL8-Pad4)") (class "Default")
      (node (ref "RL8") (pin "4") (pintype "passive"))
    )
    (net (code "224") (name "unconnected-(RL8-Pad5)") (class "Default")
      (node (ref "RL8") (pin "5") (pintype "passive"))
    )
    (net (code "225") (name "unconnected-(RL8-Pad6)") (class "Default")
      (node (ref "RL8") (pin "6") (pintype "passive"))
    )
    (net (code "226") (name "unconnected-(RL9-Pad4)") (class "Default")
      (node (ref "RL9") (pin "4") (pintype "passive"))
    )
    (net (code "227") (name "unconnected-(RL9-Pad5)") (class "Default")
      (node (ref "RL9") (pin "5") (pintype "passive"))
    )
    (net (code "228") (name "unconnected-(RL9-Pad6)") (class "Default")
      (node (ref "RL9") (pin "6") (pintype "passive"))
    )
    (net (code "229") (name "unconnected-(RL10-Pad4)") (class "Default")
      (node (ref "RL10") (pin "4") (pintype "passive"))
    )
    (net (code "230") (name "unconnected-(RL10-Pad5)") (class "Default")
      (node (ref "RL10") (pin "5") (pintype "passive"))
    )
    (net (code "231") (name "unconnected-(RL10-Pad6)") (class "Default")
      (node (ref "RL10") (pin "6") (pintype "passive"))
    )
    (net (code "232") (name "unconnected-(RL11-Pad4)") (class "Default")
      (node (ref "RL11") (pin "4") (pintype "passive"))
    )
    (net (code "233") (name "unconnected-(RL11-Pad5)") (class "Default")
      (node (ref "RL11") (pin "5") (pintype "passive"))
    )
    (net (code "234") (name "unconnected-(RL11-Pad6)") (class "Default")
      (node (ref "RL11") (pin "6") (pintype "passive"))
    )
    (net (code "235") (name "unconnected-(RL12-Pad4)") (class "Default")
      (node (ref "RL12") (pin "4") (pintype "passive"))
    )
    (net (code "236") (name "unconnected-(RL12-Pad5)") (class "Default")
      (node (ref "RL12") (pin "5") (pintype "passive"))
    )
    (net (code "237") (name "unconnected-(RL12-Pad6)") (class "Default")
      (node (ref "RL12") (pin "6") (pintype "passive"))
    )
    (net (code "238") (name "unconnected-(RL13-Pad4)") (class "Default")
      (node (ref "RL13") (pin "4") (pintype "passive"))
    )
    (net (code "239") (name "unconnected-(RL13-Pad5)") (class "Default")
      (node (ref "RL13") (pin "5") (pintype "passive"))
    )
    (net (code "240") (name "unconnected-(RL13-Pad6)") (class "Default")
      (node (ref "RL13") (pin "6") (pintype "passive"))
    )
    (net (code "241") (name "unconnected-(RL14-Pad4)") (class "Default")
      (node (ref "RL14") (pin "4") (pintype "passive"))
    )
    (net (code "242") (name "unconnected-(RL14-Pad5)") (class "Default")
      (node (ref "RL14") (pin "5") (pintype "passive"))
    )
    (net (code "243") (name "unconnected-(RL14-Pad6)") (class "Default")
      (node (ref "RL14") (pin "6") (pintype "passive"))
    )
    (net (code "244") (name "unconnected-(RL15-Pad4)") (class "Default")
      (node (ref "RL15") (pin "4") (pintype "passive"))
    )
    (net (code "245") (name "unconnected-(RL15-Pad5)") (class "Default")
      (node (ref "RL15") (pin "5") (pintype "passive"))
    )
    (net (code "246") (name "unconnected-(RL15-Pad6)") (class "Default")
      (node (ref "RL15") (pin "6") (pintype "passive"))
    )
    (net (code "247") (name "unconnected-(RL16-Pad4)") (class "Default")
      (node (ref "RL16") (pin "4") (pintype "passive"))
    )
    (net (code "248") (name "unconnected-(RL16-Pad5)") (class "Default")
      (node (ref "RL16") (pin "5") (pintype "passive"))
    )
    (net (code "249") (name "unconnected-(RL16-Pad6)") (class "Default")
      (node (ref "RL16") (pin "6") (pintype "passive"))
    )
    (net (code "250") (name "unconnected-(RL17-Pad4)") (class "Default")
      (node (ref "RL17") (pin "4") (pintype "passive"))
    )
    (net (code "251") (name "unconnected-(RL17-Pad5)") (class "Default")
      (node (ref "RL17") (pin "5") (pintype "passive"))
    )
    (net (code "252") (name "unconnected-(RL17-Pad6)") (class "Default")
      (node (ref "RL17") (pin "6") (pintype "passive"))
    )
    (net (code "253") (name "unconnected-(RL18-Pad4)") (class "Default")
      (node (ref "RL18") (pin "4") (pintype "passive"))
    )
    (net (code "254") (name "unconnected-(RL18-Pad5)") (class "Default")
      (node (ref "RL18") (pin "5") (pintype "passive"))
    )
    (net (code "255") (name "unconnected-(RL18-Pad6)") (class "Default")
      (node (ref "RL18") (pin "6") (pintype "passive"))
    )
    (net (code "256") (name "unconnected-(RL19-Pad4)") (class "Default")
      (node (ref "RL19") (pin "4") (pintype "passive"))
    )
    (net (code "257") (name "unconnected-(RL19-Pad5)") (class "Default")
      (node (ref "RL19") (pin "5") (pintype "passive"))
    )
    (net (code "258") (name "unconnected-(RL19-Pad6)") (class "Default")
      (node (ref "RL19") (pin "6") (pintype "passive"))
    )
    (net (code "259") (name "unconnected-(RL20-Pad4)") (class "Default")
      (node (ref "RL20") (pin "4") (pintype "passive"))
    )
    (net (code "260") (name "unconnected-(RL20-Pad5)") (class "Default")
      (node (ref "RL20") (pin "5") (pintype "passive"))
    )
    (net (code "261") (name "unconnected-(RL20-Pad6)") (class "Default")
      (node (ref "RL20") (pin "6") (pintype "passive"))
    )
    (net (code "262") (name "unconnected-(RL21-Pad4)") (class "Default")
      (node (ref "RL21") (pin "4") (pintype "passive"))
    )
    (net (code "263") (name "unconnected-(RL21-Pad5)") (class "Default")
      (node (ref "RL21") (pin "5") (pintype "passive"))
    )
    (net (code "264") (name "unconnected-(RL21-Pad6)") (class "Default")
      (node (ref "RL21") (pin "6") (pintype "passive"))
    )
    (net (code "265") (name "unconnected-(RL22-Pad4)") (class "Default")
      (node (ref "RL22") (pin "4") (pintype "passive"))
    )
    (net (code "266") (name "unconnected-(RL22-Pad5)") (class "Default")
      (node (ref "RL22") (pin "5") (pintype "passive"))
    )
    (net (code "267") (name "unconnected-(RL22-Pad6)") (class "Default")
      (node (ref "RL22") (pin "6") (pintype "passive"))
    )
    (net (code "268") (name "unconnected-(RL23-Pad4)") (class "Default")
      (node (ref "RL23") (pin "4") (pintype "passive"))
    )
    (net (code "269") (name "unconnected-(RL23-Pad5)") (class "Default")
      (node (ref "RL23") (pin "5") (pintype "passive"))
    )
    (net (code "270") (name "unconnected-(RL23-Pad6)") (class "Default")
      (node (ref "RL23") (pin "6") (pintype "passive"))
    )
    (net (code "271") (name "unconnected-(RL24-Pad4)") (class "Default")
      (node (ref "RL24") (pin "4") (pintype "passive"))
    )
    (net (code "272") (name "unconnected-(RL24-Pad5)") (class "Default")
      (node (ref "RL24") (pin "5") (pintype "passive"))
    )
    (net (code "273") (name "unconnected-(RL24-Pad6)") (class "Default")
      (node (ref "RL24") (pin "6") (pintype "passive"))
    )
    (net (code "274") (name "unconnected-(RL25-Pad4)") (class "Default")
      (node (ref "RL25") (pin "4") (pintype "passive"))
    )
    (net (code "275") (name "unconnected-(RL25-Pad5)") (class "Default")
      (node (ref "RL25") (pin "5") (pintype "passive"))
    )
    (net (code "276") (name "unconnected-(RL25-Pad6)") (class "Default")
      (node (ref "RL25") (pin "6") (pintype "passive"))
    )
    (net (code "277") (name "unconnected-(RL26-Pad4)") (class "Default")
      (node (ref "RL26") (pin "4") (pintype "passive"))
    )
    (net (code "278") (name "unconnected-(RL26-Pad5)") (class "Default")
      (node (ref "RL26") (pin "5") (pintype "passive"))
    )
    (net (code "279") (name "unconnected-(RL26-Pad6)") (class "Default")
      (node (ref "RL26") (pin "6") (pintype "passive"))
    )
    (net (code "280") (name "unconnected-(RL27-Pad4)") (class "Default")
      (node (ref "RL27") (pin "4") (pintype "passive"))
    )
    (net (code "281") (name "unconnected-(RL27-Pad5)") (class "Default")
      (node (ref "RL27") (pin "5") (pintype "passive"))
    )
    (net (code "282") (name "unconnected-(RL27-Pad6)") (class "Default")
      (node (ref "RL27") (pin "6") (pintype "passive"))
    )
    (net (code "283") (name "unconnected-(RL28-Pad4)") (class "Default")
      (node (ref "RL28") (pin "4") (pintype "passive"))
    )
    (net (code "284") (name "unconnected-(RL28-Pad5)") (class "Default")
      (node (ref "RL28") (pin "5") (pintype "passive"))
    )
    (net (code "285") (name "unconnected-(RL28-Pad6)") (class "Default")
      (node (ref "RL28") (pin "6") (pintype "passive"))
    )
    (net (code "286") (name "unconnected-(RL29-Pad4)") (class "Default")
      (node (ref "RL29") (pin "4") (pintype "passive"))
    )
    (net (code "287") (name "unconnected-(RL29-Pad5)") (class "Default")
      (node (ref "RL29") (pin "5") (pintype "passive"))
    )
    (net (code "288") (name "unconnected-(RL29-Pad6)") (class "Default")
      (node (ref "RL29") (pin "6") (pintype "passive"))
    )
    (net (code "289") (name "unconnected-(RL30-Pad4)") (class "Default")
      (node (ref "RL30") (pin "4") (pintype "passive"))
    )
    (net (code "290") (name "unconnected-(RL30-Pad5)") (class "Default")
      (node (ref "RL30") (pin "5") (pintype "passive"))
    )
    (net (code "291") (name "unconnected-(RL30-Pad6)") (class "Default")
      (node (ref "RL30") (pin "6") (pintype "passive"))
    )
    (net (code "292") (name "unconnected-(RL31-Pad4)") (class "Default")
      (node (ref "RL31") (pin "4") (pintype "passive"))
    )
    (net (code "293") (name "unconnected-(RL31-Pad5)") (class "Default")
      (node (ref "RL31") (pin "5") (pintype "passive"))
    )
    (net (code "294") (name "unconnected-(RL31-Pad6)") (class "Default")
      (node (ref "RL31") (pin "6") (pintype "passive"))
    )
    (net (code "295") (name "unconnected-(RL32-Pad4)") (class "Default")
      (node (ref "RL32") (pin "4") (pintype "passive"))
    )
    (net (code "296") (name "unconnected-(RL32-Pad5)") (class "Default")
      (node (ref "RL32") (pin "5") (pintype "passive"))
    )
    (net (code "297") (name "unconnected-(RL32-Pad6)") (class "Default")
      (node (ref "RL32") (pin "6") (pintype "passive"))
    )
    (net (code "298") (name "unconnected-(RL33-Pad4)") (class "Default")
      (node (ref "RL33") (pin "4") (pintype "passive"))
    )
    (net (code "299") (name "unconnected-(RL33-Pad5)") (class "Default")
      (node (ref "RL33") (pin "5") (pintype "passive"))
    )
    (net (code "300") (name "unconnected-(RL33-Pad6)") (class "Default")
      (node (ref "RL33") (pin "6") (pintype "passive"))
    )
    (net (code "301") (name "unconnected-(RL34-Pad4)") (class "Default")
      (node (ref "RL34") (pin "4") (pintype "passive"))
    )
    (net (code "302") (name "unconnected-(RL34-Pad5)") (class "Default")
      (node (ref "RL34") (pin "5") (pintype "passive"))
    )
    (net (code "303") (name "unconnected-(RL34-Pad6)") (class "Default")
      (node (ref "RL34") (pin "6") (pintype "passive"))
    )
    (net (code "304") (name "unconnected-(RL35-Pad4)") (class "Default")
      (node (ref "RL35") (pin "4") (pintype "passive"))
    )
    (net (code "305") (name "unconnected-(RL35-Pad5)") (class "Default")
      (node (ref "RL35") (pin "5") (pintype "passive"))
    )
    (net (code "306") (name "unconnected-(RL35-Pad6)") (class "Default")
      (node (ref "RL35") (pin "6") (pintype "passive"))
    )
    (net (code "307") (name "unconnected-(RL36-Pad4)") (class "Default")
      (node (ref "RL36") (pin "4") (pintype "passive"))
    )
    (net (code "308") (name "unconnected-(RL36-Pad5)") (class "Default")
      (node (ref "RL36") (pin "5") (pintype "passive"))
    )
    (net (code "309") (name "unconnected-(RL36-Pad6)") (class "Default")
      (node (ref "RL36") (pin "6") (pintype "passive"))
    )
  )
)
